# PCB-CARR-CMB-2band3.net
KiCad netlist of a schematic drawn in EAGLE
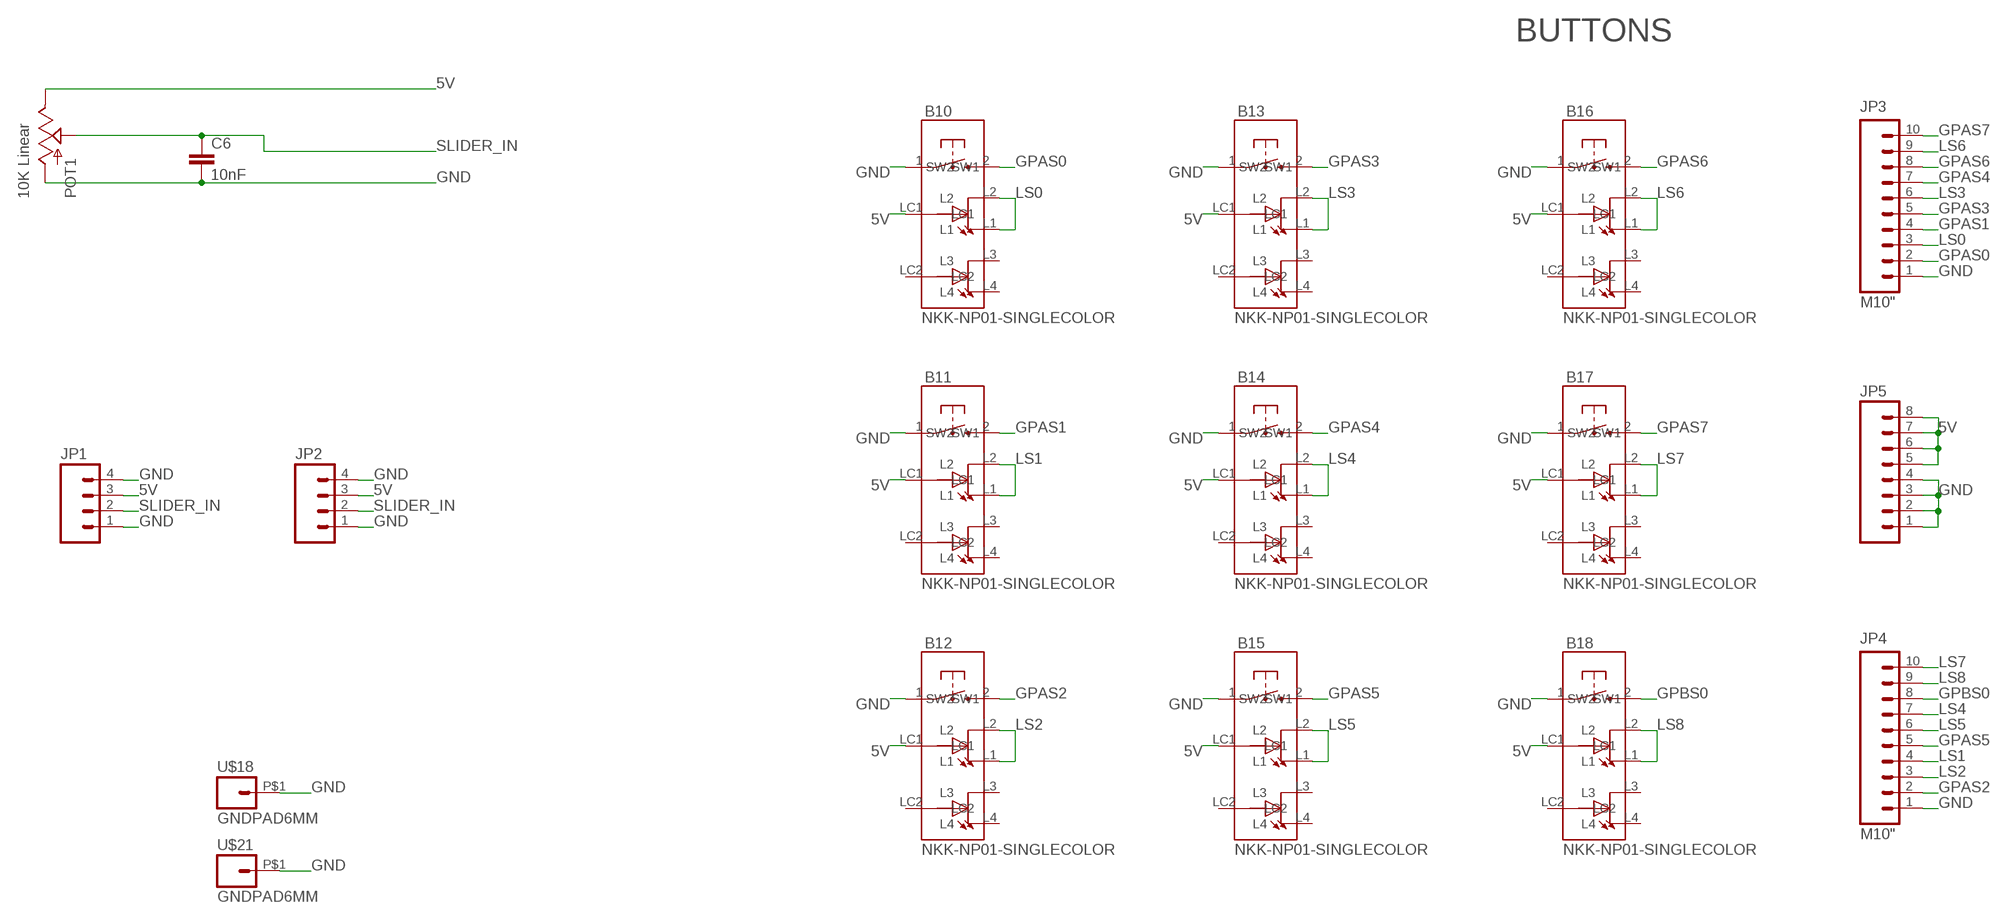
[diagram p0: schematic, sheet 1]

(export (version "E")
  (design (tool "Eeschema 10.0.6"))
  (components
    (comp (ref "B10")
      (value "NKK-NP01-SINGLECOLOR")
      (footprint "eagle-import:NKK-NP01")
      (libsource (lib "eagle-import") (part "NKK-NP01-SINGLECOLOR"))
    )
    (comp (ref "B11")
      (value "NKK-NP01-SINGLECOLOR")
      (footprint "eagle-import:NKK-NP01")
      (libsource (lib "eagle-import") (part "NKK-NP01-SINGLECOLOR"))
    )
    (comp (ref "B12")
      (value "NKK-NP01-SINGLECOLOR")
      (footprint "eagle-import:NKK-NP01")
      (libsource (lib "eagle-import") (part "NKK-NP01-SINGLECOLOR"))
    )
    (comp (ref "B13")
      (value "NKK-NP01-SINGLECOLOR")
      (footprint "eagle-import:NKK-NP01")
      (libsource (lib "eagle-import") (part "NKK-NP01-SINGLECOLOR"))
    )
    (comp (ref "B14")
      (value "NKK-NP01-SINGLECOLOR")
      (footprint "eagle-import:NKK-NP01")
      (libsource (lib "eagle-import") (part "NKK-NP01-SINGLECOLOR"))
    )
    (comp (ref "B15")
      (value "NKK-NP01-SINGLECOLOR")
      (footprint "eagle-import:NKK-NP01")
      (libsource (lib "eagle-import") (part "NKK-NP01-SINGLECOLOR"))
    )
    (comp (ref "B16")
      (value "NKK-NP01-SINGLECOLOR")
      (footprint "eagle-import:NKK-NP01")
      (libsource (lib "eagle-import") (part "NKK-NP01-SINGLECOLOR"))
    )
    (comp (ref "B17")
      (value "NKK-NP01-SINGLECOLOR")
      (footprint "eagle-import:NKK-NP01")
      (libsource (lib "eagle-import") (part "NKK-NP01-SINGLECOLOR"))
    )
    (comp (ref "B18")
      (value "NKK-NP01-SINGLECOLOR")
      (footprint "eagle-import:NKK-NP01")
      (libsource (lib "eagle-import") (part "NKK-NP01-SINGLECOLOR"))
    )
    (comp (ref "C6")
      (value "10nF")
      (footprint "eagle-import:0603-CAP")
      (libsource (lib "eagle-import") (part "CAP0603-CAP"))
    )
    (comp (ref "JP1")
      (value "M04PTH")
      (footprint "eagle-import:1X04")
      (libsource (lib "eagle-import") (part "M04PTH"))
    )
    (comp (ref "JP2")
      (value "M04PTH")
      (footprint "eagle-import:1X04")
      (libsource (lib "eagle-import") (part "M04PTH"))
    )
    (comp (ref "JP3")
      (value "M10\"")
      (footprint "eagle-import:1X10")
      (libsource (lib "eagle-import") (part "M10{dblquote}"))
    )
    (comp (ref "JP4")
      (value "M10\"")
      (footprint "eagle-import:1X10")
      (libsource (lib "eagle-import") (part "M10{dblquote}"))
    )
    (comp (ref "JP5")
      (value "M08LOCK")
      (footprint "eagle-import:1X08_LOCK")
      (libsource (lib "eagle-import") (part "M08LOCK"))
    )
    (comp (ref "POT1")
      (value "10K Linear")
      (footprint "eagle-import:SLIDER20")
      (libsource (lib "eagle-import") (part "SLIDER20"))
    )
    (comp (ref "U$18")
      (value "GNDPAD6MM")
      (footprint "eagle-import:3.2MMPAD6MM")
      (libsource (lib "eagle-import") (part "GNDPAD6MM"))
    )
    (comp (ref "U$21")
      (value "GNDPAD6MM")
      (footprint "eagle-import:3.2MMPAD6MM")
      (libsource (lib "eagle-import") (part "GNDPAD6MM"))
    )
  )
  (nets
    (net (code "1") (name "5V") (class "Default")
      (node (ref "B10") (pin "LC1") (pinfunction "LC1_LC1") (pintype "bidirectional"))
      (node (ref "B11") (pin "LC1") (pinfunction "LC1_LC1") (pintype "bidirectional"))
      (node (ref "B12") (pin "LC1") (pinfunction "LC1_LC1") (pintype "bidirectional"))
      (node (ref "B13") (pin "LC1") (pinfunction "LC1_LC1") (pintype "bidirectional"))
      (node (ref "B14") (pin "LC1") (pinfunction "LC1_LC1") (pintype "bidirectional"))
      (node (ref "B15") (pin "LC1") (pinfunction "LC1_LC1") (pintype "bidirectional"))
      (node (ref "B16") (pin "LC1") (pinfunction "LC1_LC1") (pintype "bidirectional"))
      (node (ref "B17") (pin "LC1") (pinfunction "LC1_LC1") (pintype "bidirectional"))
      (node (ref "B18") (pin "LC1") (pinfunction "LC1_LC1") (pintype "bidirectional"))
      (node (ref "JP1") (pin "3") (pinfunction "3_3") (pintype "passive"))
      (node (ref "JP2") (pin "3") (pinfunction "3_3") (pintype "passive"))
      (node (ref "JP5") (pin "5") (pinfunction "5_5") (pintype "passive"))
      (node (ref "JP5") (pin "6") (pinfunction "6_6") (pintype "passive"))
      (node (ref "JP5") (pin "7") (pinfunction "7_7") (pintype "passive"))
      (node (ref "JP5") (pin "8") (pinfunction "8_8") (pintype "passive"))
      (node (ref "POT1") (pin "1") (pinfunction "E_1") (pintype "passive"))
    )
    (net (code "2") (name "GND") (class "Default")
      (node (ref "B10") (pin "1") (pinfunction "SW1_1") (pintype "bidirectional"))
      (node (ref "B11") (pin "1") (pinfunction "SW1_1") (pintype "bidirectional"))
      (node (ref "B12") (pin "1") (pinfunction "SW1_1") (pintype "bidirectional"))
      (node (ref "B13") (pin "1") (pinfunction "SW1_1") (pintype "bidirectional"))
      (node (ref "B14") (pin "1") (pinfunction "SW1_1") (pintype "bidirectional"))
      (node (ref "B15") (pin "1") (pinfunction "SW1_1") (pintype "bidirectional"))
      (node (ref "B16") (pin "1") (pinfunction "SW1_1") (pintype "bidirectional"))
      (node (ref "B17") (pin "1") (pinfunction "SW1_1") (pintype "bidirectional"))
      (node (ref "B18") (pin "1") (pinfunction "SW1_1") (pintype "bidirectional"))
      (node (ref "C6") (pin "2") (pinfunction "2_2") (pintype "passive"))
      (node (ref "JP1") (pin "1") (pinfunction "1_1") (pintype "passive"))
      (node (ref "JP1") (pin "4") (pinfunction "4_4") (pintype "passive"))
      (node (ref "JP2") (pin "1") (pinfunction "1_1") (pintype "passive"))
      (node (ref "JP2") (pin "4") (pinfunction "4_4") (pintype "passive"))
      (node (ref "JP3") (pin "1") (pinfunction "1_1") (pintype "passive"))
      (node (ref "JP4") (pin "1") (pinfunction "1_1") (pintype "passive"))
      (node (ref "JP5") (pin "1") (pinfunction "1_1") (pintype "passive"))
      (node (ref "JP5") (pin "2") (pinfunction "2_2") (pintype "passive"))
      (node (ref "JP5") (pin "3") (pinfunction "3_3") (pintype "passive"))
      (node (ref "JP5") (pin "4") (pinfunction "4_4") (pintype "passive"))
      (node (ref "POT1") (pin "3") (pinfunction "A_3") (pintype "passive"))
      (node (ref "U$18") (pin "P$1") (pinfunction "1_P$1") (pintype "passive"))
      (node (ref "U$21") (pin "P$1") (pinfunction "1_P$1") (pintype "passive"))
    )
    (net (code "3") (name "GPAS0") (class "Default")
      (node (ref "B10") (pin "2") (pinfunction "SW2_2") (pintype "bidirectional"))
      (node (ref "JP3") (pin "2") (pinfunction "2_2") (pintype "passive"))
    )
    (net (code "4") (name "GPAS1") (class "Default")
      (node (ref "B11") (pin "2") (pinfunction "SW2_2") (pintype "bidirectional"))
      (node (ref "JP3") (pin "4") (pinfunction "4_4") (pintype "passive"))
    )
    (net (code "5") (name "GPAS2") (class "Default")
      (node (ref "B12") (pin "2") (pinfunction "SW2_2") (pintype "bidirectional"))
      (node (ref "JP4") (pin "2") (pinfunction "2_2") (pintype "passive"))
    )
    (net (code "6") (name "GPAS3") (class "Default")
      (node (ref "B13") (pin "2") (pinfunction "SW2_2") (pintype "bidirectional"))
      (node (ref "JP3") (pin "5") (pinfunction "5_5") (pintype "passive"))
    )
    (net (code "7") (name "GPAS4") (class "Default")
      (node (ref "B14") (pin "2") (pinfunction "SW2_2") (pintype "bidirectional"))
      (node (ref "JP3") (pin "7") (pinfunction "7_7") (pintype "passive"))
    )
    (net (code "8") (name "GPAS5") (class "Default")
      (node (ref "B15") (pin "2") (pinfunction "SW2_2") (pintype "bidirectional"))
      (node (ref "JP4") (pin "5") (pinfunction "5_5") (pintype "passive"))
    )
    (net (code "9") (name "GPAS6") (class "Default")
      (node (ref "B16") (pin "2") (pinfunction "SW2_2") (pintype "bidirectional"))
      (node (ref "JP3") (pin "8") (pinfunction "8_8") (pintype "passive"))
    )
    (net (code "10") (name "GPAS7") (class "Default")
      (node (ref "B17") (pin "2") (pinfunction "SW2_2") (pintype "bidirectional"))
      (node (ref "JP3") (pin "10") (pinfunction "10_10") (pintype "passive"))
    )
    (net (code "11") (name "GPBS0") (class "Default")
      (node (ref "B18") (pin "2") (pinfunction "SW2_2") (pintype "bidirectional"))
      (node (ref "JP4") (pin "8") (pinfunction "8_8") (pintype "passive"))
    )
    (net (code "12") (name "LS0") (class "Default")
      (node (ref "B10") (pin "L1") (pinfunction "L1_L1") (pintype "bidirectional"))
      (node (ref "B10") (pin "L2") (pinfunction "L2_L2") (pintype "bidirectional"))
      (node (ref "JP3") (pin "3") (pinfunction "3_3") (pintype "passive"))
    )
    (net (code "13") (name "LS1") (class "Default")
      (node (ref "B11") (pin "L1") (pinfunction "L1_L1") (pintype "bidirectional"))
      (node (ref "B11") (pin "L2") (pinfunction "L2_L2") (pintype "bidirectional"))
      (node (ref "JP4") (pin "4") (pinfunction "4_4") (pintype "passive"))
    )
    (net (code "14") (name "LS2") (class "Default")
      (node (ref "B12") (pin "L1") (pinfunction "L1_L1") (pintype "bidirectional"))
      (node (ref "B12") (pin "L2") (pinfunction "L2_L2") (pintype "bidirectional"))
      (node (ref "JP4") (pin "3") (pinfunction "3_3") (pintype "passive"))
    )
    (net (code "15") (name "LS3") (class "Default")
      (node (ref "B13") (pin "L1") (pinfunction "L1_L1") (pintype "bidirectional"))
      (node (ref "B13") (pin "L2") (pinfunction "L2_L2") (pintype "bidirectional"))
      (node (ref "JP3") (pin "6") (pinfunction "6_6") (pintype "passive"))
    )
    (net (code "16") (name "LS4") (class "Default")
      (node (ref "B14") (pin "L1") (pinfunction "L1_L1") (pintype "bidirectional"))
      (node (ref "B14") (pin "L2") (pinfunction "L2_L2") (pintype "bidirectional"))
      (node (ref "JP4") (pin "7") (pinfunction "7_7") (pintype "passive"))
    )
    (net (code "17") (name "LS5") (class "Default")
      (node (ref "B15") (pin "L1") (pinfunction "L1_L1") (pintype "bidirectional"))
      (node (ref "B15") (pin "L2") (pinfunction "L2_L2") (pintype "bidirectional"))
      (node (ref "JP4") (pin "6") (pinfunction "6_6") (pintype "passive"))
    )
    (net (code "18") (name "LS6") (class "Default")
      (node (ref "B16") (pin "L1") (pinfunction "L1_L1") (pintype "bidirectional"))
      (node (ref "B16") (pin "L2") (pinfunction "L2_L2") (pintype "bidirectional"))
      (node (ref "JP3") (pin "9") (pinfunction "9_9") (pintype "passive"))
    )
    (net (code "19") (name "LS7") (class "Default")
      (node (ref "B17") (pin "L1") (pinfunction "L1_L1") (pintype "bidirectional"))
      (node (ref "B17") (pin "L2") (pinfunction "L2_L2") (pintype "bidirectional"))
      (node (ref "JP4") (pin "10") (pinfunction "10_10") (pintype "passive"))
    )
    (net (code "20") (name "LS8") (class "Default")
      (node (ref "B18") (pin "L1") (pinfunction "L1_L1") (pintype "bidirectional"))
      (node (ref "B18") (pin "L2") (pinfunction "L2_L2") (pintype "bidirectional"))
      (node (ref "JP4") (pin "9") (pinfunction "9_9") (pintype "passive"))
    )
    (net (code "21") (name "SLIDER_IN") (class "Default")
      (node (ref "C6") (pin "1") (pinfunction "1_1") (pintype "passive"))
      (node (ref "JP1") (pin "2") (pinfunction "2_2") (pintype "passive"))
      (node (ref "JP2") (pin "2") (pinfunction "2_2") (pintype "passive"))
      (node (ref "POT1") (pin "2A") (pinfunction "S_2A") (pintype "passive"))
    )
    (net (code "22") (name "unconnected-(B10-PadL3)") (class "Default")
      (node (ref "B10") (pin "L3") (pinfunction "L3_L3") (pintype "bidirectional"))
    )
    (net (code "23") (name "unconnected-(B10-PadL4)") (class "Default")
      (node (ref "B10") (pin "L4") (pinfunction "L4_L4") (pintype "bidirectional"))
    )
    (net (code "24") (name "unconnected-(B10-PadLC2)") (class "Default")
      (node (ref "B10") (pin "LC2") (pinfunction "LC2_LC2") (pintype "bidirectional"))
    )
    (net (code "25") (name "unconnected-(B11-PadL3)") (class "Default")
      (node (ref "B11") (pin "L3") (pinfunction "L3_L3") (pintype "bidirectional"))
    )
    (net (code "26") (name "unconnected-(B11-PadL4)") (class "Default")
      (node (ref "B11") (pin "L4") (pinfunction "L4_L4") (pintype "bidirectional"))
    )
    (net (code "27") (name "unconnected-(B11-PadLC2)") (class "Default")
      (node (ref "B11") (pin "LC2") (pinfunction "LC2_LC2") (pintype "bidirectional"))
    )
    (net (code "28") (name "unconnected-(B12-PadL3)") (class "Default")
      (node (ref "B12") (pin "L3") (pinfunction "L3_L3") (pintype "bidirectional"))
    )
    (net (code "29") (name "unconnected-(B12-PadL4)") (class "Default")
      (node (ref "B12") (pin "L4") (pinfunction "L4_L4") (pintype "bidirectional"))
    )
    (net (code "30") (name "unconnected-(B12-PadLC2)") (class "Default")
      (node (ref "B12") (pin "LC2") (pinfunction "LC2_LC2") (pintype "bidirectional"))
    )
    (net (code "31") (name "unconnected-(B13-PadL3)") (class "Default")
      (node (ref "B13") (pin "L3") (pinfunction "L3_L3") (pintype "bidirectional"))
    )
    (net (code "32") (name "unconnected-(B13-PadL4)") (class "Default")
      (node (ref "B13") (pin "L4") (pinfunction "L4_L4") (pintype "bidirectional"))
    )
    (net (code "33") (name "unconnected-(B13-PadLC2)") (class "Default")
      (node (ref "B13") (pin "LC2") (pinfunction "LC2_LC2") (pintype "bidirectional"))
    )
    (net (code "34") (name "unconnected-(B14-PadL3)") (class "Default")
      (node (ref "B14") (pin "L3") (pinfunction "L3_L3") (pintype "bidirectional"))
    )
    (net (code "35") (name "unconnected-(B14-PadL4)") (class "Default")
      (node (ref "B14") (pin "L4") (pinfunction "L4_L4") (pintype "bidirectional"))
    )
    (net (code "36") (name "unconnected-(B14-PadLC2)") (class "Default")
      (node (ref "B14") (pin "LC2") (pinfunction "LC2_LC2") (pintype "bidirectional"))
    )
    (net (code "37") (name "unconnected-(B15-PadL3)") (class "Default")
      (node (ref "B15") (pin "L3") (pinfunction "L3_L3") (pintype "bidirectional"))
    )
    (net (code "38") (name "unconnected-(B15-PadL4)") (class "Default")
      (node (ref "B15") (pin "L4") (pinfunction "L4_L4") (pintype "bidirectional"))
    )
    (net (code "39") (name "unconnected-(B15-PadLC2)") (class "Default")
      (node (ref "B15") (pin "LC2") (pinfunction "LC2_LC2") (pintype "bidirectional"))
    )
    (net (code "40") (name "unconnected-(B16-PadL3)") (class "Default")
      (node (ref "B16") (pin "L3") (pinfunction "L3_L3") (pintype "bidirectional"))
    )
    (net (code "41") (name "unconnected-(B16-PadL4)") (class "Default")
      (node (ref "B16") (pin "L4") (pinfunction "L4_L4") (pintype "bidirectional"))
    )
    (net (code "42") (name "unconnected-(B16-PadLC2)") (class "Default")
      (node (ref "B16") (pin "LC2") (pinfunction "LC2_LC2") (pintype "bidirectional"))
    )
    (net (code "43") (name "unconnected-(B17-PadL3)") (class "Default")
      (node (ref "B17") (pin "L3") (pinfunction "L3_L3") (pintype "bidirectional"))
    )
    (net (code "44") (name "unconnected-(B17-PadL4)") (class "Default")
      (node (ref "B17") (pin "L4") (pinfunction "L4_L4") (pintype "bidirectional"))
    )
    (net (code "45") (name "unconnected-(B17-PadLC2)") (class "Default")
      (node (ref "B17") (pin "LC2") (pinfunction "LC2_LC2") (pintype "bidirectional"))
    )
    (net (code "46") (name "unconnected-(B18-PadL3)") (class "Default")
      (node (ref "B18") (pin "L3") (pinfunction "L3_L3") (pintype "bidirectional"))
    )
    (net (code "47") (name "unconnected-(B18-PadL4)") (class "Default")
      (node (ref "B18") (pin "L4") (pinfunction "L4_L4") (pintype "bidirectional"))
    )
    (net (code "48") (name "unconnected-(B18-PadLC2)") (class "Default")
      (node (ref "B18") (pin "LC2") (pinfunction "LC2_LC2") (pintype "bidirectional"))
    )
  )
)
